# untitled.net
KiCad netlist of a schematic drawn in EAGLE
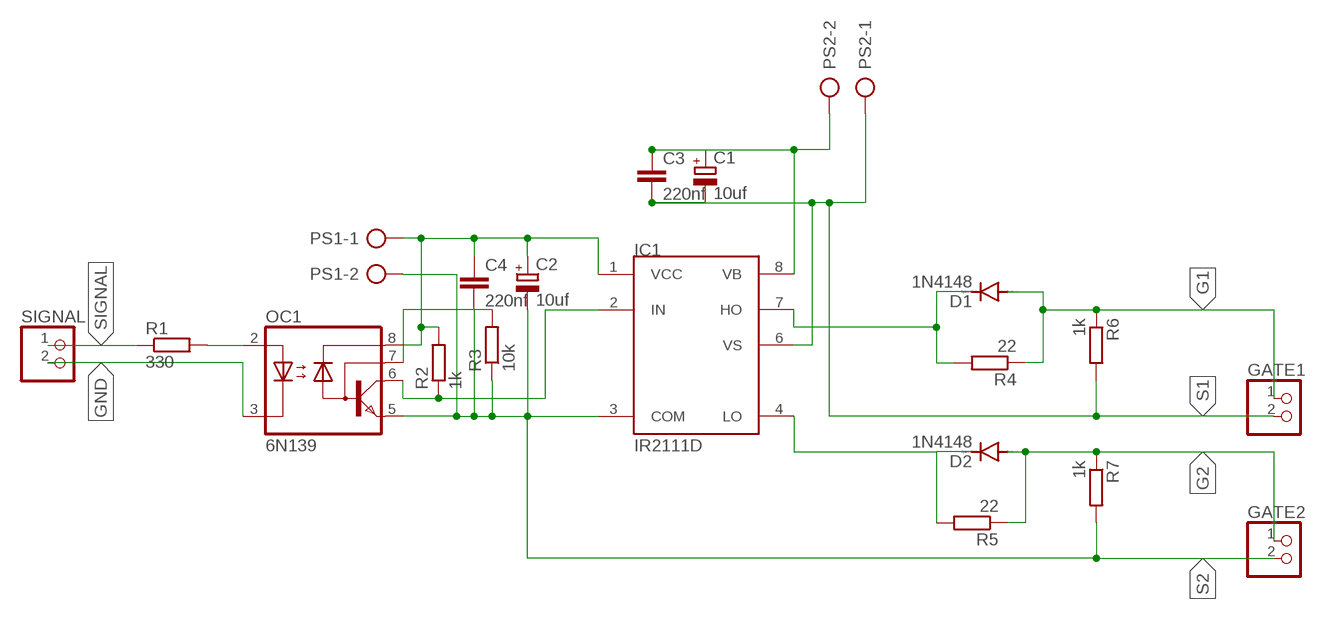
[diagram p0: schematic, sheet 1]

(export (version "E")
  (design (tool "Eeschema 10.0.6"))
  (components
    (comp (ref "C1")
      (value "10uf")
      (footprint "eagle-import:E2,5-6E")
      (libsource (lib "eagle-import") (part "CPOL-EUE2,5-6E"))
    )
    (comp (ref "C2")
      (value "10uf")
      (footprint "eagle-import:E2,5-6E")
      (libsource (lib "eagle-import") (part "CPOL-EUE2,5-6E"))
    )
    (comp (ref "C3")
      (value "220nf")
      (footprint "eagle-import:C025-025X050")
      (libsource (lib "eagle-import") (part "C-EU025-025X050"))
    )
    (comp (ref "C4")
      (value "220nf")
      (footprint "eagle-import:C025-025X050")
      (libsource (lib "eagle-import") (part "C-EU025-025X050"))
    )
    (comp (ref "D1")
      (value "1N4148")
      (footprint "eagle-import:DO35-10")
      (libsource (lib "eagle-import") (part "1N4148DO35-10"))
    )
    (comp (ref "D2")
      (value "1N4148")
      (footprint "eagle-import:DO35-10")
      (libsource (lib "eagle-import") (part "1N4148DO35-10"))
    )
    (comp (ref "GATE1")
      (value "PINHD-1X2")
      (footprint "eagle-import:1X02")
      (libsource (lib "eagle-import") (part "PINHD-1X2"))
    )
    (comp (ref "GATE2")
      (value "PINHD-1X2")
      (footprint "eagle-import:1X02")
      (libsource (lib "eagle-import") (part "PINHD-1X2"))
    )
    (comp (ref "IC1")
      (value "IR2111D")
      (footprint "eagle-import:DIL08")
      (libsource (lib "eagle-import") (part "IR2111D"))
    )
    (comp (ref "OC1")
      (value "6N139")
      (footprint "eagle-import:DIL08")
      (libsource (lib "eagle-import") (part "6N139"))
    )
    (comp (ref "PS1")
      (value "AK300/2")
      (footprint "eagle-import:AK300_2")
      (libsource (lib "eagle-import") (part "AK300/2"))
    )
    (comp (ref "PS2")
      (value "AK300/2")
      (footprint "eagle-import:AK300_2")
      (libsource (lib "eagle-import") (part "AK300/2"))
    )
    (comp (ref "R1")
      (value "330")
      (footprint "eagle-import:0204_7")
      (libsource (lib "eagle-import") (part "R-EU_0204/7"))
    )
    (comp (ref "R2")
      (value "1k")
      (footprint "eagle-import:0204_7")
      (libsource (lib "eagle-import") (part "R-EU_0204/7"))
    )
    (comp (ref "R3")
      (value "10k")
      (footprint "eagle-import:0204_7")
      (libsource (lib "eagle-import") (part "R-EU_0204/7"))
    )
    (comp (ref "R4")
      (value "22")
      (footprint "eagle-import:0204_7")
      (libsource (lib "eagle-import") (part "R-EU_0204/7"))
    )
    (comp (ref "R5")
      (value "22")
      (footprint "eagle-import:0204_7")
      (libsource (lib "eagle-import") (part "R-EU_0204/7"))
    )
    (comp (ref "R6")
      (value "1k")
      (footprint "eagle-import:0204_7")
      (libsource (lib "eagle-import") (part "R-EU_0204/7"))
    )
    (comp (ref "R7")
      (value "1k")
      (footprint "eagle-import:0204_7")
      (libsource (lib "eagle-import") (part "R-EU_0204/7"))
    )
    (comp (ref "SIGNAL")
      (value "PINHD-1X2")
      (footprint "eagle-import:1X02")
      (libsource (lib "eagle-import") (part "PINHD-1X2"))
    )
  )
  (nets
    (net (code "1") (name "G1") (class "Default")
      (node (ref "D1") (pin "A") (pinfunction "A_A") (pintype "passive"))
      (node (ref "GATE1") (pin "1") (pinfunction "1_1") (pintype "passive"))
      (node (ref "R4") (pin "1") (pinfunction "1_1") (pintype "passive"))
      (node (ref "R6") (pin "1") (pinfunction "1_1") (pintype "passive"))
    )
    (net (code "2") (name "G2") (class "Default")
      (node (ref "D2") (pin "A") (pinfunction "A_A") (pintype "passive"))
      (node (ref "GATE2") (pin "1") (pinfunction "1_1") (pintype "passive"))
      (node (ref "R5") (pin "1") (pinfunction "1_1") (pintype "passive"))
      (node (ref "R7") (pin "1") (pinfunction "1_1") (pintype "passive"))
    )
    (net (code "3") (name "GND") (class "Default")
      (node (ref "OC1") (pin "3") (pinfunction "C_3") (pintype "passive"))
      (node (ref "SIGNAL") (pin "2") (pinfunction "2_2") (pintype "passive"))
    )
    (net (code "4") (name "Net-(IC1-HO)") (class "Default")
      (node (ref "D1") (pin "C") (pinfunction "C_C") (pintype "passive"))
      (node (ref "IC1") (pin "7") (pinfunction "HO_7") (pintype "output"))
      (node (ref "R4") (pin "2") (pinfunction "2_2") (pintype "passive"))
    )
    (net (code "5") (name "Net-(IC1-IN)") (class "Default")
      (node (ref "IC1") (pin "2") (pinfunction "IN_2") (pintype "input"))
      (node (ref "OC1") (pin "6") (pinfunction "VO_6") (pintype "passive"))
      (node (ref "R2") (pin "1") (pinfunction "1_1") (pintype "passive"))
    )
    (net (code "6") (name "Net-(IC1-LO)") (class "Default")
      (node (ref "D2") (pin "C") (pinfunction "C_C") (pintype "passive"))
      (node (ref "IC1") (pin "4") (pinfunction "LO_4") (pintype "output"))
      (node (ref "R5") (pin "2") (pinfunction "2_2") (pintype "passive"))
    )
    (net (code "7") (name "Net-(IC1-VB)") (class "Default")
      (node (ref "C1") (pin "+") (pinfunction "+_+") (pintype "passive"))
      (node (ref "C3") (pin "1") (pinfunction "1_1") (pintype "passive"))
      (node (ref "IC1") (pin "8") (pinfunction "VB_8") (pintype "power_in"))
      (node (ref "PS2") (pin "2") (pinfunction "KL_2") (pintype "passive"))
    )
    (net (code "8") (name "Net-(IC1-VCC)") (class "Default")
      (node (ref "C2") (pin "+") (pinfunction "+_+") (pintype "passive"))
      (node (ref "C4") (pin "1") (pinfunction "1_1") (pintype "passive"))
      (node (ref "IC1") (pin "1") (pinfunction "VCC_1") (pintype "power_in"))
      (node (ref "OC1") (pin "8") (pinfunction "VCC_8") (pintype "passive"))
      (node (ref "PS1") (pin "1") (pinfunction "KL_1") (pintype "passive"))
      (node (ref "R2") (pin "2") (pinfunction "2_2") (pintype "passive"))
    )
    (net (code "9") (name "Net-(OC1-A)") (class "Default")
      (node (ref "OC1") (pin "2") (pinfunction "A_2") (pintype "passive"))
      (node (ref "R1") (pin "2") (pinfunction "2_2") (pintype "passive"))
    )
    (net (code "10") (name "Net-(OC1-VB)") (class "Default")
      (node (ref "OC1") (pin "7") (pinfunction "VB_7") (pintype "passive"))
      (node (ref "R3") (pin "2") (pinfunction "2_2") (pintype "passive"))
    )
    (net (code "11") (name "S1") (class "Default")
      (node (ref "C1") (pin "-") (pinfunction "-_-") (pintype "passive"))
      (node (ref "C3") (pin "2") (pinfunction "2_2") (pintype "passive"))
      (node (ref "GATE1") (pin "2") (pinfunction "2_2") (pintype "passive"))
      (node (ref "IC1") (pin "6") (pinfunction "VS_6") (pintype "power_in"))
      (node (ref "PS2") (pin "1") (pinfunction "KL_1") (pintype "passive"))
      (node (ref "R6") (pin "2") (pinfunction "2_2") (pintype "passive"))
    )
    (net (code "12") (name "S2") (class "Default")
      (node (ref "C2") (pin "-") (pinfunction "-_-") (pintype "passive"))
      (node (ref "C4") (pin "2") (pinfunction "2_2") (pintype "passive"))
      (node (ref "GATE2") (pin "2") (pinfunction "2_2") (pintype "passive"))
      (node (ref "IC1") (pin "3") (pinfunction "COM_3") (pintype "power_in"))
      (node (ref "OC1") (pin "5") (pinfunction "GND_5") (pintype "passive"))
      (node (ref "PS1") (pin "2") (pinfunction "KL_2") (pintype "passive"))
      (node (ref "R3") (pin "1") (pinfunction "1_1") (pintype "passive"))
      (node (ref "R7") (pin "2") (pinfunction "2_2") (pintype "passive"))
    )
    (net (code "13") (name "SIGNAL") (class "Default")
      (node (ref "R1") (pin "1") (pinfunction "1_1") (pintype "passive"))
      (node (ref "SIGNAL") (pin "1") (pinfunction "1_1") (pintype "passive"))
    )
  )
)
